# flip-flop.net
KiCad netlist of a schematic drawn in EAGLE
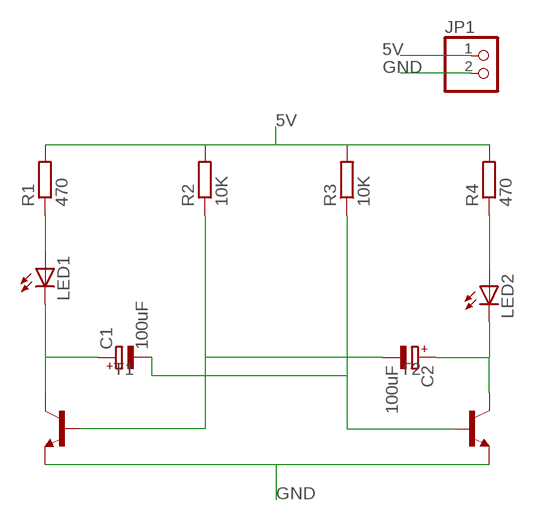
[diagram p0: schematic, sheet 1]

(export (version "E")
  (design (tool "Eeschema 10.0.6"))
  (components
    (comp (ref "C1")
      (value "100uF")
      (footprint "eagle-import:E2,5-6")
      (libsource (lib "eagle-import") (part "CPOL-EUE2.5-6"))
    )
    (comp (ref "C2")
      (value "100uF")
      (footprint "eagle-import:E2,5-6")
      (libsource (lib "eagle-import") (part "CPOL-EUE2.5-6"))
    )
    (comp (ref "JP1")
      (value "PINHD-1X2")
      (footprint "eagle-import:1X02")
      (libsource (lib "eagle-import") (part "PINHD-1X2"))
    )
    (comp (ref "LED1")
      (value "LED3MM")
      (footprint "eagle-import:LED3MM")
      (libsource (lib "eagle-import") (part "LED3MM"))
    )
    (comp (ref "LED2")
      (value "LED3MM")
      (footprint "eagle-import:LED3MM")
      (libsource (lib "eagle-import") (part "LED3MM"))
    )
    (comp (ref "R1")
      (value "470")
      (footprint "eagle-import:0207_7")
      (libsource (lib "eagle-import") (part "R-EU_0207/7"))
    )
    (comp (ref "R2")
      (value "10K")
      (footprint "eagle-import:0207_7")
      (libsource (lib "eagle-import") (part "R-EU_0207/7"))
    )
    (comp (ref "R3")
      (value "10K")
      (footprint "eagle-import:0207_7")
      (libsource (lib "eagle-import") (part "R-EU_0207/7"))
    )
    (comp (ref "R4")
      (value "470")
      (footprint "eagle-import:0207_7")
      (libsource (lib "eagle-import") (part "R-EU_0207/7"))
    )
    (comp (ref "T1")
      (value "BC547-NPN-TO92-CBE")
      (footprint "eagle-import:TO92-CBE")
      (libsource (lib "eagle-import") (part "-NPN-TO92-CBEBC547"))
    )
    (comp (ref "T2")
      (value "BC547-NPN-TO92-CBE")
      (footprint "eagle-import:TO92-CBE")
      (libsource (lib "eagle-import") (part "-NPN-TO92-CBEBC547"))
    )
  )
  (nets
    (net (code "1") (name "/5V") (class "Default")
      (node (ref "JP1") (pin "1") (pinfunction "1_1") (pintype "passive"))
      (node (ref "R1") (pin "2") (pinfunction "2_2") (pintype "passive"))
      (node (ref "R2") (pin "2") (pinfunction "2_2") (pintype "passive"))
      (node (ref "R3") (pin "2") (pinfunction "2_2") (pintype "passive"))
      (node (ref "R4") (pin "2") (pinfunction "2_2") (pintype "passive"))
    )
    (net (code "2") (name "/GND") (class "Default")
      (node (ref "JP1") (pin "2") (pinfunction "2_2") (pintype "passive"))
      (node (ref "T1") (pin "E") (pinfunction "E_E") (pintype "passive"))
      (node (ref "T2") (pin "E") (pinfunction "E_E") (pintype "passive"))
    )
    (net (code "3") (name "Net-(C1-Pad-)") (class "Default")
      (node (ref "C1") (pin "-") (pinfunction "-_-") (pintype "passive"))
      (node (ref "R3") (pin "1") (pinfunction "1_1") (pintype "passive"))
      (node (ref "T2") (pin "B") (pinfunction "B_B") (pintype "passive"))
    )
    (net (code "4") (name "Net-(C2-Pad-)") (class "Default")
      (node (ref "C2") (pin "-") (pinfunction "-_-") (pintype "passive"))
      (node (ref "R2") (pin "1") (pinfunction "1_1") (pintype "passive"))
      (node (ref "T1") (pin "B") (pinfunction "B_B") (pintype "passive"))
    )
    (net (code "5") (name "Net-(LED1-C)") (class "Default")
      (node (ref "C1") (pin "+") (pinfunction "+_+") (pintype "passive"))
      (node (ref "LED1") (pin "K") (pinfunction "C_K") (pintype "passive"))
      (node (ref "T1") (pin "C") (pinfunction "C_C") (pintype "passive"))
    )
    (net (code "6") (name "Net-(LED1-PadA)") (class "Default")
      (node (ref "LED1") (pin "A") (pinfunction "A_A") (pintype "passive"))
      (node (ref "R1") (pin "1") (pinfunction "1_1") (pintype "passive"))
    )
    (net (code "7") (name "Net-(LED2-C)") (class "Default")
      (node (ref "C2") (pin "+") (pinfunction "+_+") (pintype "passive"))
      (node (ref "LED2") (pin "K") (pinfunction "C_K") (pintype "passive"))
      (node (ref "T2") (pin "C") (pinfunction "C_C") (pintype "passive"))
    )
    (net (code "8") (name "Net-(LED2-PadA)") (class "Default")
      (node (ref "LED2") (pin "A") (pinfunction "A_A") (pintype "passive"))
      (node (ref "R4") (pin "1") (pinfunction "1_1") (pintype "passive"))
    )
  )
)
